# GSM.net
KiCad netlist of a schematic drawn in EAGLE
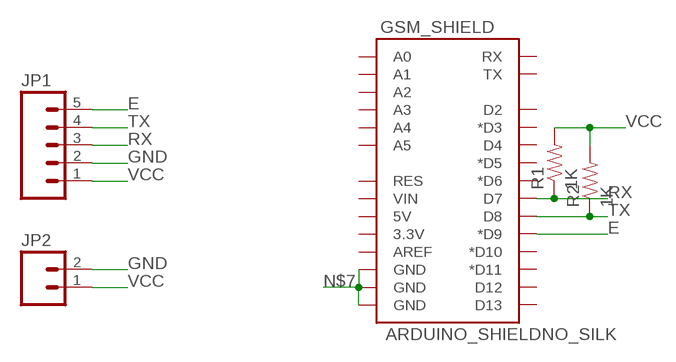
[diagram p0: schematic, sheet 1]

(export (version "E")
  (design (tool "Eeschema 10.0.6"))
  (components
    (comp (ref "GSM_SHIELD")
      (value "ARDUINO_SHIELDNO_SILK")
      (footprint "eagle-import:DUEMILANOVE_VIAS")
      (libsource (lib "eagle-import") (part "ARDUINO_SHIELDNO_SILK"))
    )
    (comp (ref "JP1")
      (value "M05PTH_LONGPADS")
      (footprint "eagle-import:1X05_LONGPADS")
      (libsource (lib "eagle-import") (part "M05PTH_LONGPADS"))
    )
    (comp (ref "JP2")
      (value "M02PTH3")
      (footprint "eagle-import:1X02_LONGPADS")
      (libsource (lib "eagle-import") (part "M02PTH3"))
    )
    (comp (ref "R1")
      (value "1K")
      (footprint "eagle-import:AXIAL-0.4")
      (libsource (lib "eagle-import") (part "RESISTORPTH-1/4W"))
    )
    (comp (ref "R2")
      (value "1K")
      (footprint "eagle-import:AXIAL-0.4")
      (libsource (lib "eagle-import") (part "RESISTORPTH-1/4W"))
    )
  )
  (nets
    (net (code "1") (name "/E") (class "Default")
      (node (ref "GSM_SHIELD") (pin "D9") (pinfunction "*D9_D9") (pintype "bidirectional"))
      (node (ref "JP1") (pin "5") (pinfunction "5_5") (pintype "passive"))
    )
    (net (code "2") (name "/GND") (class "Default")
      (node (ref "JP1") (pin "2") (pinfunction "2_2") (pintype "passive"))
      (node (ref "JP2") (pin "2") (pinfunction "2_2") (pintype "passive"))
    )
    (net (code "3") (name "/N$7") (class "Default")
      (node (ref "GSM_SHIELD") (pin "GND@0") (pinfunction "GND_GND@0") (pintype "bidirectional"))
      (node (ref "GSM_SHIELD") (pin "GND@1") (pinfunction "GND_GND@1") (pintype "bidirectional"))
      (node (ref "GSM_SHIELD") (pin "GND@2") (pinfunction "GND_GND@2") (pintype "bidirectional"))
    )
    (net (code "4") (name "/RX") (class "Default")
      (node (ref "GSM_SHIELD") (pin "D7") (pinfunction "D7_D7") (pintype "bidirectional"))
      (node (ref "JP1") (pin "3") (pinfunction "3_3") (pintype "passive"))
      (node (ref "R1") (pin "P$1") (pinfunction "1_P$1") (pintype "passive"))
    )
    (net (code "5") (name "/TX") (class "Default")
      (node (ref "GSM_SHIELD") (pin "D8") (pinfunction "D8_D8") (pintype "bidirectional"))
      (node (ref "JP1") (pin "4") (pinfunction "4_4") (pintype "passive"))
      (node (ref "R2") (pin "P$1") (pinfunction "1_P$1") (pintype "passive"))
    )
    (net (code "6") (name "/VCC") (class "Default")
      (node (ref "JP1") (pin "1") (pinfunction "1_1") (pintype "passive"))
      (node (ref "JP2") (pin "1") (pinfunction "1_1") (pintype "passive"))
      (node (ref "R1") (pin "P$2") (pinfunction "2_P$2") (pintype "passive"))
      (node (ref "R2") (pin "P$2") (pinfunction "2_P$2") (pintype "passive"))
    )
    (net (code "7") (name "unconnected-(GSM_SHIELD-*D3-PadD3)") (class "Default")
      (node (ref "GSM_SHIELD") (pin "D3") (pinfunction "*D3_D3") (pintype "bidirectional"))
    )
    (net (code "8") (name "unconnected-(GSM_SHIELD-*D5-PadD5)") (class "Default")
      (node (ref "GSM_SHIELD") (pin "D5") (pinfunction "*D5_D5") (pintype "bidirectional"))
    )
    (net (code "9") (name "unconnected-(GSM_SHIELD-*D6-PadD6)") (class "Default")
      (node (ref "GSM_SHIELD") (pin "D6") (pinfunction "*D6_D6") (pintype "bidirectional"))
    )
    (net (code "10") (name "unconnected-(GSM_SHIELD-*D10-PadD10)") (class "Default")
      (node (ref "GSM_SHIELD") (pin "D10") (pinfunction "*D10_D10") (pintype "bidirectional"))
    )
    (net (code "11") (name "unconnected-(GSM_SHIELD-*D11-PadD11)") (class "Default")
      (node (ref "GSM_SHIELD") (pin "D11") (pinfunction "*D11_D11") (pintype "bidirectional"))
    )
    (net (code "12") (name "unconnected-(GSM_SHIELD-Pad3.3V)") (class "Default")
      (node (ref "GSM_SHIELD") (pin "3.3V") (pinfunction "3.3V_3.3V") (pintype "bidirectional"))
    )
    (net (code "13") (name "unconnected-(GSM_SHIELD-Pad5V)") (class "Default")
      (node (ref "GSM_SHIELD") (pin "5V") (pinfunction "5V_5V") (pintype "bidirectional"))
    )
    (net (code "14") (name "unconnected-(GSM_SHIELD-PadA0)") (class "Default")
      (node (ref "GSM_SHIELD") (pin "A0") (pinfunction "A0_A0") (pintype "bidirectional"))
    )
    (net (code "15") (name "unconnected-(GSM_SHIELD-PadA1)") (class "Default")
      (node (ref "GSM_SHIELD") (pin "A1") (pinfunction "A1_A1") (pintype "bidirectional"))
    )
    (net (code "16") (name "unconnected-(GSM_SHIELD-PadA2)") (class "Default")
      (node (ref "GSM_SHIELD") (pin "A2") (pinfunction "A2_A2") (pintype "bidirectional"))
    )
    (net (code "17") (name "unconnected-(GSM_SHIELD-PadA3)") (class "Default")
      (node (ref "GSM_SHIELD") (pin "A3") (pinfunction "A3_A3") (pintype "bidirectional"))
    )
    (net (code "18") (name "unconnected-(GSM_SHIELD-PadA4)") (class "Default")
      (node (ref "GSM_SHIELD") (pin "A4") (pinfunction "A4_A4") (pintype "bidirectional"))
    )
    (net (code "19") (name "unconnected-(GSM_SHIELD-PadA5)") (class "Default")
      (node (ref "GSM_SHIELD") (pin "A5") (pinfunction "A5_A5") (pintype "bidirectional"))
    )
    (net (code "20") (name "unconnected-(GSM_SHIELD-PadAREF)") (class "Default")
      (node (ref "GSM_SHIELD") (pin "AREF") (pinfunction "AREF_AREF") (pintype "bidirectional"))
    )
    (net (code "21") (name "unconnected-(GSM_SHIELD-PadD2)") (class "Default")
      (node (ref "GSM_SHIELD") (pin "D2") (pinfunction "D2_D2") (pintype "bidirectional"))
    )
    (net (code "22") (name "unconnected-(GSM_SHIELD-PadD4)") (class "Default")
      (node (ref "GSM_SHIELD") (pin "D4") (pinfunction "D4_D4") (pintype "bidirectional"))
    )
    (net (code "23") (name "unconnected-(GSM_SHIELD-PadD12)") (class "Default")
      (node (ref "GSM_SHIELD") (pin "D12") (pinfunction "D12_D12") (pintype "bidirectional"))
    )
    (net (code "24") (name "unconnected-(GSM_SHIELD-PadD13)") (class "Default")
      (node (ref "GSM_SHIELD") (pin "D13") (pinfunction "D13_D13") (pintype "bidirectional"))
    )
    (net (code "25") (name "unconnected-(GSM_SHIELD-PadRES)") (class "Default")
      (node (ref "GSM_SHIELD") (pin "RES") (pinfunction "RES_RES") (pintype "bidirectional"))
    )
    (net (code "26") (name "unconnected-(GSM_SHIELD-PadRX)") (class "Default")
      (node (ref "GSM_SHIELD") (pin "RX") (pinfunction "RX_RX") (pintype "bidirectional"))
    )
    (net (code "27") (name "unconnected-(GSM_SHIELD-PadTX)") (class "Default")
      (node (ref "GSM_SHIELD") (pin "TX") (pinfunction "TX_TX") (pintype "bidirectional"))
    )
    (net (code "28") (name "unconnected-(GSM_SHIELD-PadVIN)") (class "Default")
      (node (ref "GSM_SHIELD") (pin "VIN") (pinfunction "VIN_VIN") (pintype "bidirectional"))
    )
  )
)
